# ATM90E3x-DB.net
KiCad netlist of a schematic drawn in Altium Designer
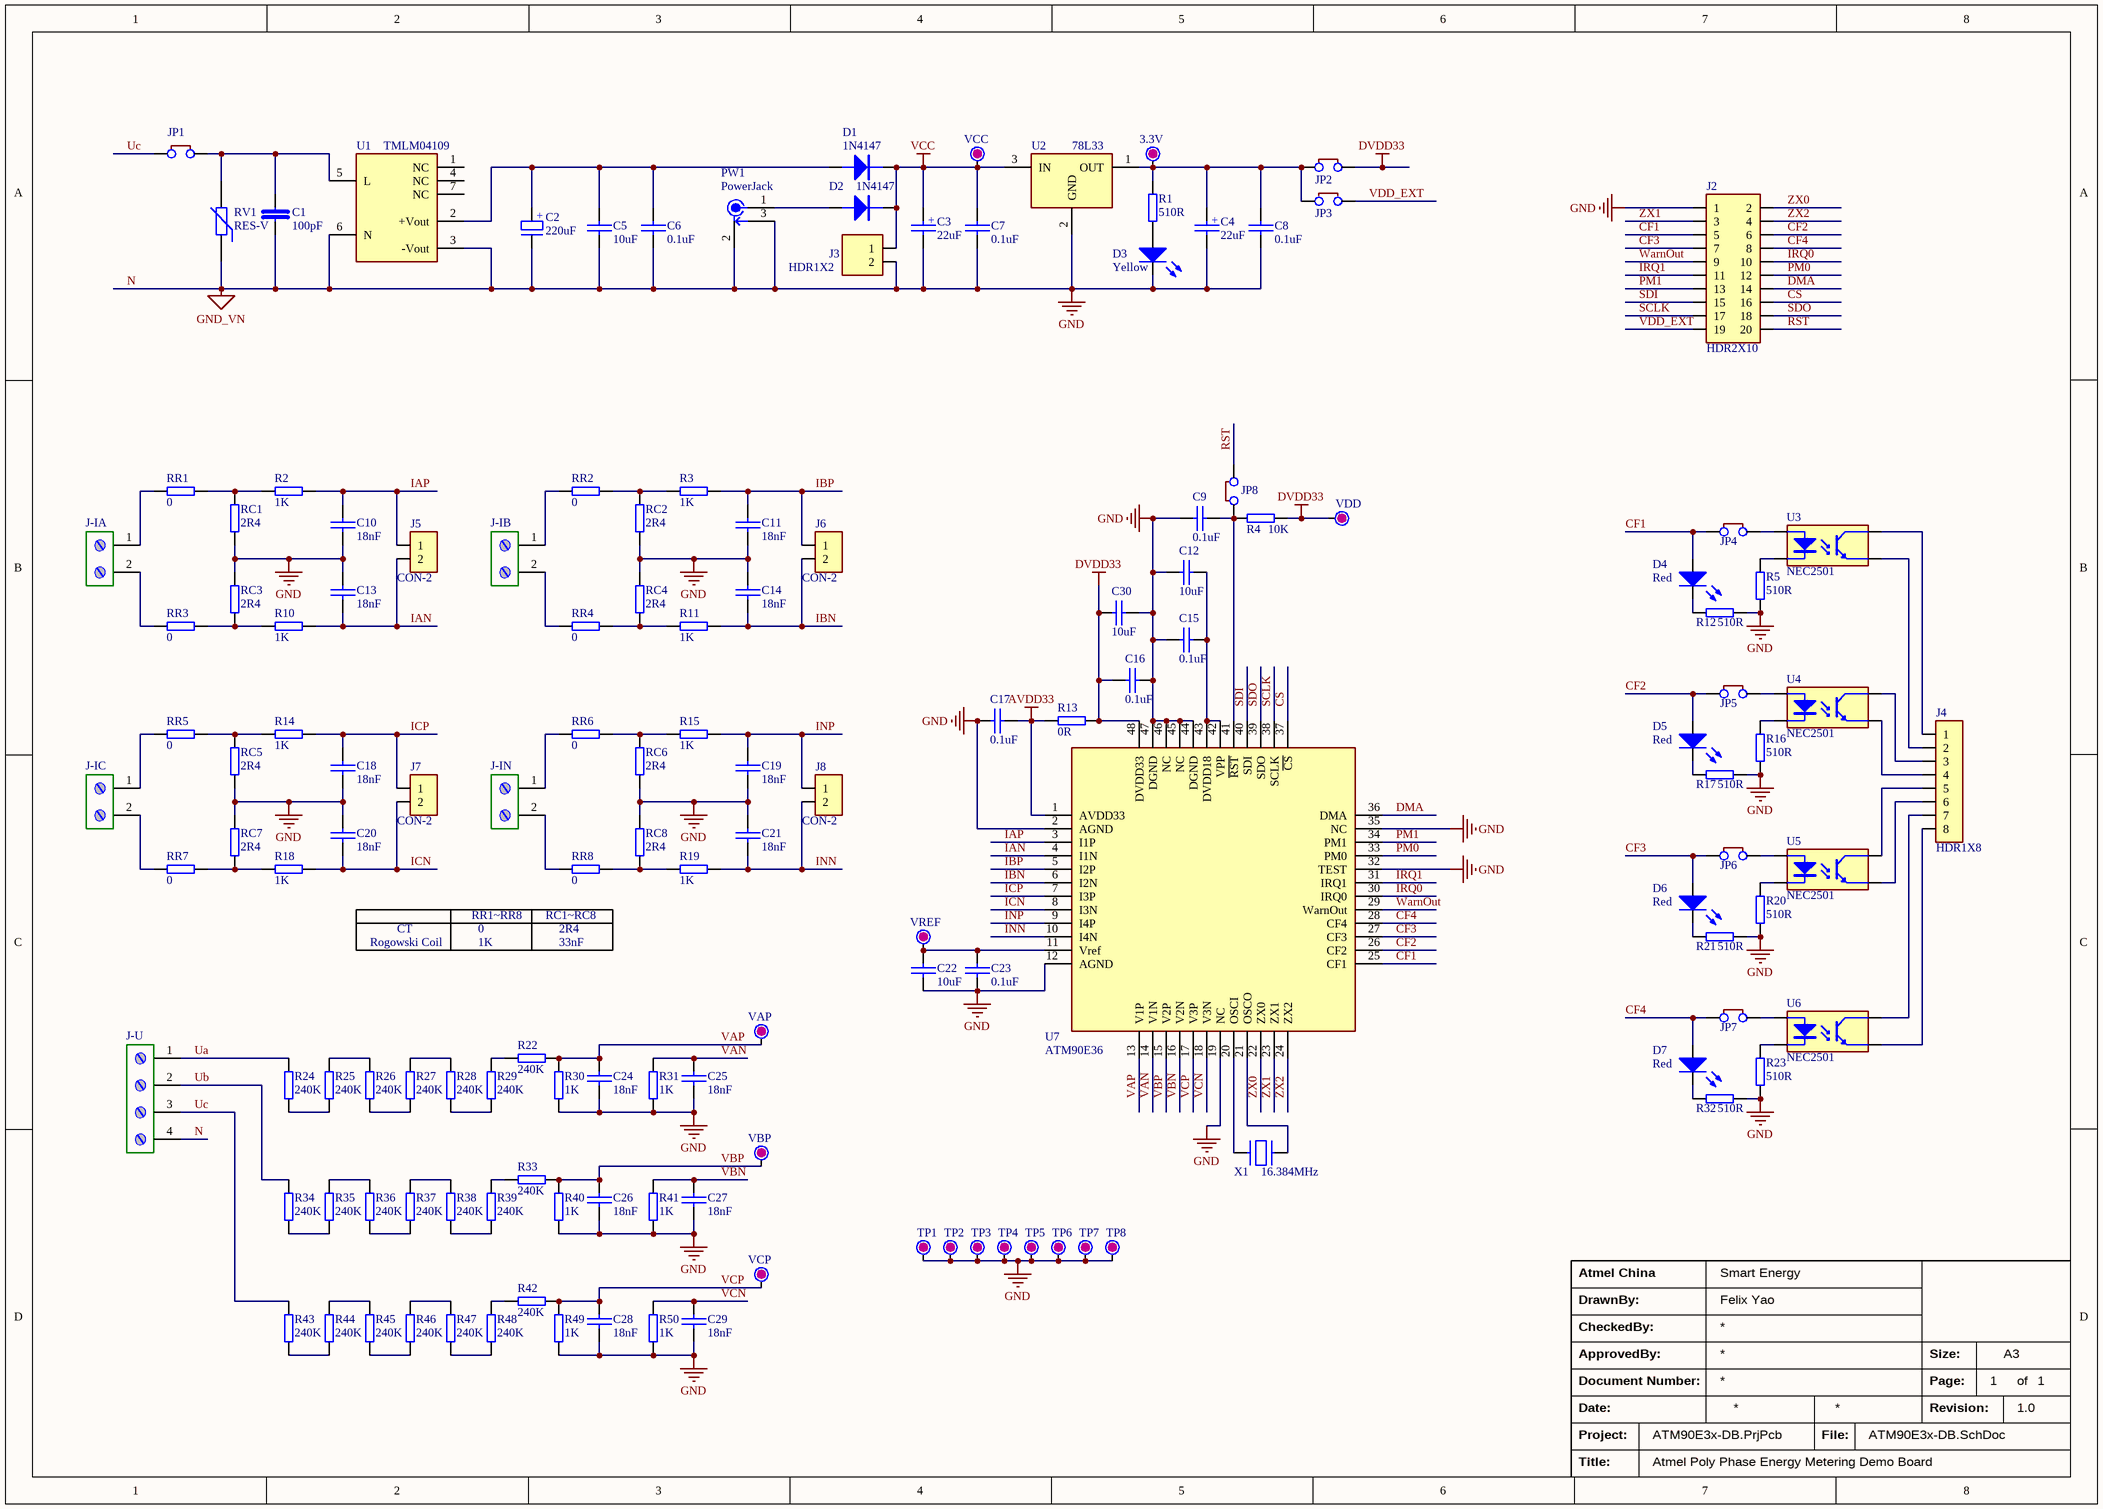
[diagram p0: ATM90E3x-DB.SchDoc]

(export (version "E")
  (design (tool "Eeschema 10.0.6"))
  (components
    (comp (ref "3.3V") (value "~") (footprint "TP") (libsource (lib "SchLib(AD10)") (part "TEST-POINT")))
    (comp (ref "C1")
      (value "100pF")
      (footprint "C_FILM_600")
      (libsource (lib "SchLib(AD10)") (part "CAP-FILM"))
    )
    (comp (ref "C2")
      (value "220uF")
      (footprint "C_ALUM_MIX_10x10")
      (libsource (lib "SchLib(AD10)") (part "CAP-ALUM"))
    )
    (comp (ref "C3")
      (value "22uF")
      (footprint "C_TANT_B3528")
      (libsource (lib "SchLib(AD10)") (part "CAP-TANT"))
    )
    (comp (ref "C4")
      (value "22uF")
      (footprint "C_TANT_B3528")
      (libsource (lib "SchLib(AD10)") (part "CAP-TANT"))
    )
    (comp (ref "C5") (value "10uF") (footprint "C0805") (libsource (lib "SchLib(AD10)") (part "CAP")))
    (comp (ref "C6") (value "0.1uF") (footprint "C0805") (libsource (lib "SchLib(AD10)") (part "CAP")))
    (comp (ref "C7") (value "0.1uF") (footprint "C0805") (libsource (lib "SchLib(AD10)") (part "CAP")))
    (comp (ref "C8") (value "0.1uF") (footprint "C0805") (libsource (lib "SchLib(AD10)") (part "CAP")))
    (comp (ref "C9") (value "0.1uF") (footprint "C0603") (libsource (lib "SchLib(AD10)") (part "CAP")))
    (comp (ref "C10") (value "18nF") (footprint "C0805") (libsource (lib "SchLib(AD10)") (part "CAP")))
    (comp (ref "C11") (value "18nF") (footprint "C0805") (libsource (lib "SchLib(AD10)") (part "CAP")))
    (comp (ref "C12") (value "10uF") (footprint "C0805") (libsource (lib "SchLib(AD10)") (part "CAP")))
    (comp (ref "C13") (value "18nF") (footprint "C0805") (libsource (lib "SchLib(AD10)") (part "CAP")))
    (comp (ref "C14") (value "18nF") (footprint "C0805") (libsource (lib "SchLib(AD10)") (part "CAP")))
    (comp (ref "C15") (value "0.1uF") (footprint "C0603") (libsource (lib "SchLib(AD10)") (part "CAP")))
    (comp (ref "C16") (value "0.1uF") (footprint "C0603") (libsource (lib "SchLib(AD10)") (part "CAP")))
    (comp (ref "C17") (value "0.1uF") (footprint "C0603") (libsource (lib "SchLib(AD10)") (part "CAP")))
    (comp (ref "C18") (value "18nF") (footprint "C0805") (libsource (lib "SchLib(AD10)") (part "CAP")))
    (comp (ref "C19") (value "18nF") (footprint "C0805") (libsource (lib "SchLib(AD10)") (part "CAP")))
    (comp (ref "C20") (value "18nF") (footprint "C0805") (libsource (lib "SchLib(AD10)") (part "CAP")))
    (comp (ref "C21") (value "18nF") (footprint "C0805") (libsource (lib "SchLib(AD10)") (part "CAP")))
    (comp (ref "C22") (value "10uF") (footprint "C0805") (libsource (lib "SchLib(AD10)") (part "CAP")))
    (comp (ref "C23") (value "0.1uF") (footprint "C0603") (libsource (lib "SchLib(AD10)") (part "CAP")))
    (comp (ref "C24") (value "18nF") (footprint "C0805") (libsource (lib "SchLib(AD10)") (part "CAP")))
    (comp (ref "C25") (value "18nF") (footprint "C0805") (libsource (lib "SchLib(AD10)") (part "CAP")))
    (comp (ref "C26") (value "18nF") (footprint "C0805") (libsource (lib "SchLib(AD10)") (part "CAP")))
    (comp (ref "C27") (value "18nF") (footprint "C0805") (libsource (lib "SchLib(AD10)") (part "CAP")))
    (comp (ref "C28") (value "18nF") (footprint "C0805") (libsource (lib "SchLib(AD10)") (part "CAP")))
    (comp (ref "C29") (value "18nF") (footprint "C0805") (libsource (lib "SchLib(AD10)") (part "CAP")))
    (comp (ref "C30") (value "10uF") (footprint "C0805") (libsource (lib "SchLib(AD10)") (part "CAP")))
    (comp (ref "D1")
      (value "1N4147")
      (footprint "SMA DO-214AC")
      (libsource (lib "SchLib(AD10)") (part "DIODE"))
    )
    (comp (ref "D2")
      (value "1N4147")
      (footprint "SMA DO-214AC")
      (libsource (lib "SchLib(AD10)") (part "DIODE"))
    )
    (comp (ref "D3") (value "Yellow") (footprint "LED-0805Y") (libsource (lib "SchLib(AD10)") (part "LED")))
    (comp (ref "D4") (value "Red") (footprint "LED-0805R") (libsource (lib "SchLib(AD10)") (part "LED")))
    (comp (ref "D5") (value "Red") (footprint "LED-0805R") (libsource (lib "SchLib(AD10)") (part "LED")))
    (comp (ref "D6") (value "Red") (footprint "LED-0805R") (libsource (lib "SchLib(AD10)") (part "LED")))
    (comp (ref "D7") (value "Red") (footprint "LED-0805R") (libsource (lib "SchLib(AD10)") (part "LED")))
    (comp (ref "J-IA")
      (value "~")
      (footprint "TE-1776119-2")
      (libsource (lib "SchLib(AD10)") (part "Terminal-Screw-2"))
    )
    (comp (ref "J-IB")
      (value "~")
      (footprint "TE-1776119-2")
      (libsource (lib "SchLib(AD10)") (part "Terminal-Screw-2"))
    )
    (comp (ref "J-IC")
      (value "~")
      (footprint "TE-1776119-2")
      (libsource (lib "SchLib(AD10)") (part "Terminal-Screw-2"))
    )
    (comp (ref "J-IN")
      (value "~")
      (footprint "TE-1776119-2")
      (libsource (lib "SchLib(AD10)") (part "Terminal-Screw-2"))
    )
    (comp (ref "J-U")
      (value "~")
      (footprint "TE-282843-4")
      (libsource (lib "SchLib(AD10)") (part "Terminal-Screw-4"))
    )
    (comp (ref "J2")
      (value "HDR2X10")
      (footprint "HDR2X10")
      (libsource (lib "SchLib(AD10)") (part "HDR2X10"))
    )
    (comp (ref "J3") (value "HDR1X2") (footprint "HDR1X2") (libsource (lib "SchLib(AD10)") (part "HDR1X2")))
    (comp (ref "J4") (value "HDR1X8") (footprint "HDR1X8") (libsource (lib "SchLib(AD10)") (part "HDR1X8")))
    (comp (ref "J5")
      (value "CON-2")
      (footprint "HDR1X2(uper)")
      (libsource (lib "SchLib(AD10)") (part "CON-2"))
    )
    (comp (ref "J6")
      (value "CON-2")
      (footprint "HDR1X2(uper)")
      (libsource (lib "SchLib(AD10)") (part "CON-2"))
    )
    (comp (ref "J7")
      (value "CON-2")
      (footprint "HDR1X2(uper)")
      (libsource (lib "SchLib(AD10)") (part "CON-2"))
    )
    (comp (ref "J8")
      (value "CON-2")
      (footprint "HDR1X2(uper)")
      (libsource (lib "SchLib(AD10)") (part "CON-2"))
    )
    (comp (ref "JP1") (value "JMP") (footprint "JMP-SMD") (libsource (lib "SchLib(AD10)") (part "JMP")))
    (comp (ref "JP2") (value "JMP") (footprint "JMP") (libsource (lib "SchLib(AD10)") (part "JMP")))
    (comp (ref "JP3") (value "JMP") (footprint "JMP") (libsource (lib "SchLib(AD10)") (part "JMP")))
    (comp (ref "JP4") (value "JMP") (footprint "JMP") (libsource (lib "SchLib(AD10)") (part "JMP")))
    (comp (ref "JP5") (value "JMP") (footprint "JMP") (libsource (lib "SchLib(AD10)") (part "JMP")))
    (comp (ref "JP6") (value "JMP") (footprint "JMP") (libsource (lib "SchLib(AD10)") (part "JMP")))
    (comp (ref "JP7") (value "JMP") (footprint "JMP") (libsource (lib "SchLib(AD10)") (part "JMP")))
    (comp (ref "JP8") (value "JMP") (footprint "JMP") (libsource (lib "SchLib(AD10)") (part "JMP")))
    (comp (ref "PW1")
      (value "PowerJack")
      (footprint "PowerJacket2.5")
      (libsource (lib "SchLib(AD10)") (part "PowerJack"))
    )
    (comp (ref "R1") (value "510R") (footprint "R0805") (libsource (lib "SchLib(AD10)") (part "RES")))
    (comp (ref "R2") (value "1K") (footprint "R0805") (libsource (lib "SchLib(AD10)") (part "RES")))
    (comp (ref "R3") (value "1K") (footprint "R0805") (libsource (lib "SchLib(AD10)") (part "RES")))
    (comp (ref "R4") (value "10K") (footprint "R0603") (libsource (lib "SchLib(AD10)") (part "RES")))
    (comp (ref "R5") (value "510R") (footprint "R0805") (libsource (lib "SchLib(AD10)") (part "RES")))
    (comp (ref "R10") (value "1K") (footprint "R0805") (libsource (lib "SchLib(AD10)") (part "RES")))
    (comp (ref "R11") (value "1K") (footprint "R0805") (libsource (lib "SchLib(AD10)") (part "RES")))
    (comp (ref "R12") (value "510R") (footprint "R0805") (libsource (lib "SchLib(AD10)") (part "RES")))
    (comp (ref "R13") (value "0R") (footprint "R0603") (libsource (lib "SchLib(AD10)") (part "RES")))
    (comp (ref "R14") (value "1K") (footprint "R0805") (libsource (lib "SchLib(AD10)") (part "RES")))
    (comp (ref "R15") (value "1K") (footprint "R0805") (libsource (lib "SchLib(AD10)") (part "RES")))
    (comp (ref "R16") (value "510R") (footprint "R0805") (libsource (lib "SchLib(AD10)") (part "RES")))
    (comp (ref "R17") (value "510R") (footprint "R0805") (libsource (lib "SchLib(AD10)") (part "RES")))
    (comp (ref "R18") (value "1K") (footprint "R0805") (libsource (lib "SchLib(AD10)") (part "RES")))
    (comp (ref "R19") (value "1K") (footprint "R0805") (libsource (lib "SchLib(AD10)") (part "RES")))
    (comp (ref "R20") (value "510R") (footprint "R0805") (libsource (lib "SchLib(AD10)") (part "RES")))
    (comp (ref "R21") (value "510R") (footprint "R0805") (libsource (lib "SchLib(AD10)") (part "RES")))
    (comp (ref "R22") (value "240K") (footprint "R1206") (libsource (lib "SchLib(AD10)") (part "RES")))
    (comp (ref "R23") (value "510R") (footprint "R0805") (libsource (lib "SchLib(AD10)") (part "RES")))
    (comp (ref "R24") (value "240K") (footprint "R1206") (libsource (lib "SchLib(AD10)") (part "RES")))
    (comp (ref "R25") (value "240K") (footprint "R1206") (libsource (lib "SchLib(AD10)") (part "RES")))
    (comp (ref "R26") (value "240K") (footprint "R1206") (libsource (lib "SchLib(AD10)") (part "RES")))
    (comp (ref "R27") (value "240K") (footprint "R1206") (libsource (lib "SchLib(AD10)") (part "RES")))
    (comp (ref "R28") (value "240K") (footprint "R1206") (libsource (lib "SchLib(AD10)") (part "RES")))
    (comp (ref "R29") (value "240K") (footprint "R1206") (libsource (lib "SchLib(AD10)") (part "RES")))
    (comp (ref "R30") (value "1K") (footprint "R0805") (libsource (lib "SchLib(AD10)") (part "RES")))
    (comp (ref "R31") (value "1K") (footprint "R0805") (libsource (lib "SchLib(AD10)") (part "RES")))
    (comp (ref "R32") (value "510R") (footprint "R0805") (libsource (lib "SchLib(AD10)") (part "RES")))
    (comp (ref "R33") (value "240K") (footprint "R1206") (libsource (lib "SchLib(AD10)") (part "RES")))
    (comp (ref "R34") (value "240K") (footprint "R1206") (libsource (lib "SchLib(AD10)") (part "RES")))
    (comp (ref "R35") (value "240K") (footprint "R1206") (libsource (lib "SchLib(AD10)") (part "RES")))
    (comp (ref "R36") (value "240K") (footprint "R1206") (libsource (lib "SchLib(AD10)") (part "RES")))
    (comp (ref "R37") (value "240K") (footprint "R1206") (libsource (lib "SchLib(AD10)") (part "RES")))
    (comp (ref "R38") (value "240K") (footprint "R1206") (libsource (lib "SchLib(AD10)") (part "RES")))
    (comp (ref "R39") (value "240K") (footprint "R1206") (libsource (lib "SchLib(AD10)") (part "RES")))
    (comp (ref "R40") (value "1K") (footprint "R0805") (libsource (lib "SchLib(AD10)") (part "RES")))
    (comp (ref "R41") (value "1K") (footprint "R0805") (libsource (lib "SchLib(AD10)") (part "RES")))
    (comp (ref "R42") (value "240K") (footprint "R1206") (libsource (lib "SchLib(AD10)") (part "RES")))
    (comp (ref "R43") (value "240K") (footprint "R1206") (libsource (lib "SchLib(AD10)") (part "RES")))
    (comp (ref "R44") (value "240K") (footprint "R1206") (libsource (lib "SchLib(AD10)") (part "RES")))
    (comp (ref "R45") (value "240K") (footprint "R1206") (libsource (lib "SchLib(AD10)") (part "RES")))
    (comp (ref "R46") (value "240K") (footprint "R1206") (libsource (lib "SchLib(AD10)") (part "RES")))
    (comp (ref "R47") (value "240K") (footprint "R1206") (libsource (lib "SchLib(AD10)") (part "RES")))
    (comp (ref "R48") (value "240K") (footprint "R1206") (libsource (lib "SchLib(AD10)") (part "RES")))
    (comp (ref "R49") (value "1K") (footprint "R0805") (libsource (lib "SchLib(AD10)") (part "RES")))
    (comp (ref "R50") (value "1K") (footprint "R0805") (libsource (lib "SchLib(AD10)") (part "RES")))
    (comp (ref "RC1") (value "2R4") (footprint "R0805") (libsource (lib "SchLib(AD10)") (part "RES")))
    (comp (ref "RC2") (value "2R4") (footprint "R0805") (libsource (lib "SchLib(AD10)") (part "RES")))
    (comp (ref "RC3") (value "2R4") (footprint "R0805") (libsource (lib "SchLib(AD10)") (part "RES")))
    (comp (ref "RC4") (value "2R4") (footprint "R0805") (libsource (lib "SchLib(AD10)") (part "RES")))
    (comp (ref "RC5") (value "2R4") (footprint "R0805") (libsource (lib "SchLib(AD10)") (part "RES")))
    (comp (ref "RC6") (value "2R4") (footprint "R0805") (libsource (lib "SchLib(AD10)") (part "RES")))
    (comp (ref "RC7") (value "2R4") (footprint "R0805") (libsource (lib "SchLib(AD10)") (part "RES")))
    (comp (ref "RC8") (value "2R4") (footprint "R0805") (libsource (lib "SchLib(AD10)") (part "RES")))
    (comp (ref "RR1") (value "0") (footprint "R0805") (libsource (lib "SchLib(AD10)") (part "RES")))
    (comp (ref "RR2") (value "0") (footprint "R0805") (libsource (lib "SchLib(AD10)") (part "RES")))
    (comp (ref "RR3") (value "0") (footprint "R0805") (libsource (lib "SchLib(AD10)") (part "RES")))
    (comp (ref "RR4") (value "0") (footprint "R0805") (libsource (lib "SchLib(AD10)") (part "RES")))
    (comp (ref "RR5") (value "0") (footprint "R0805") (libsource (lib "SchLib(AD10)") (part "RES")))
    (comp (ref "RR6") (value "0") (footprint "R0805") (libsource (lib "SchLib(AD10)") (part "RES")))
    (comp (ref "RR7") (value "0") (footprint "R0805") (libsource (lib "SchLib(AD10)") (part "RES")))
    (comp (ref "RR8") (value "0") (footprint "R0805") (libsource (lib "SchLib(AD10)") (part "RES")))
    (comp (ref "RV1")
      (value "RES-V")
      (footprint "VDRS10P510BSE")
      (libsource (lib "SchLib(AD10)") (part "RES-V"))
    )
    (comp (ref "TP1") (value "GND") (footprint "TP") (libsource (lib "SchLib(AD10)") (part "TEST-POINT")))
    (comp (ref "TP2") (value "GND") (footprint "TP") (libsource (lib "SchLib(AD10)") (part "TEST-POINT")))
    (comp (ref "TP3") (value "GND") (footprint "TP") (libsource (lib "SchLib(AD10)") (part "TEST-POINT")))
    (comp (ref "TP4") (value "GND") (footprint "TP") (libsource (lib "SchLib(AD10)") (part "TEST-POINT")))
    (comp (ref "TP5") (value "GND") (footprint "TP-SMD") (libsource (lib "SchLib(AD10)") (part "TEST-POINT")))
    (comp (ref "TP6") (value "GND") (footprint "TP-SMD") (libsource (lib "SchLib(AD10)") (part "TEST-POINT")))
    (comp (ref "TP7") (value "GND") (footprint "TP-SMD") (libsource (lib "SchLib(AD10)") (part "TEST-POINT")))
    (comp (ref "TP8") (value "GND") (footprint "TP-SMD") (libsource (lib "SchLib(AD10)") (part "TEST-POINT")))
    (comp (ref "U1")
      (value "TMLM04109")
      (footprint "TMLM04112")
      (libsource (lib "SchLib(AD10)") (part "TMLM04112"))
    )
    (comp (ref "U2") (value "78L33") (footprint "SOT-89") (libsource (lib "SchLib(AD10)") (part "78LXX")))
    (comp (ref "U3")
      (value "NEC2501")
      (footprint "PS2501L-1")
      (libsource (lib "SchLib(AD10)") (part "NEC2501"))
    )
    (comp (ref "U4")
      (value "NEC2501")
      (footprint "PS2501L-1")
      (libsource (lib "SchLib(AD10)") (part "NEC2501"))
    )
    (comp (ref "U5")
      (value "NEC2501")
      (footprint "PS2501L-1")
      (libsource (lib "SchLib(AD10)") (part "NEC2501"))
    )
    (comp (ref "U6")
      (value "NEC2501")
      (footprint "PS2501L-1")
      (libsource (lib "SchLib(AD10)") (part "NEC2501"))
    )
    (comp (ref "U7")
      (value "ATM90E36")
      (footprint "TQFP-48(7x7)")
      (description "ATM90E3X")
      (libsource (lib "SchLib(AD10)") (part "ATM90E3X"))
    )
    (comp (ref "VAP") (value "~") (footprint "TP") (libsource (lib "SchLib(AD10)") (part "TEST-POINT")))
    (comp (ref "VBP") (value "~") (footprint "TP") (libsource (lib "SchLib(AD10)") (part "TEST-POINT")))
    (comp (ref "VCC") (value "~") (footprint "TP") (libsource (lib "SchLib(AD10)") (part "TEST-POINT")))
    (comp (ref "VCP") (value "~") (footprint "TP") (libsource (lib "SchLib(AD10)") (part "TEST-POINT")))
    (comp (ref "VDD") (value "~") (footprint "TP") (libsource (lib "SchLib(AD10)") (part "TEST-POINT")))
    (comp (ref "VREF") (value "~") (footprint "TP") (libsource (lib "SchLib(AD10)") (part "TEST-POINT")))
    (comp (ref "X1")
      (value "16.384MHz")
      (footprint "XTAL-MIX-49")
      (libsource (lib "SchLib(AD10)") (part "XTAL-T"))
    )
  )
  (nets
    (net (code "1") (name "/CF1") (class "Default")
      (node (ref "D4") (pin "A") (pinfunction "A_A") (pintype "passive"))
      (node (ref "J2") (pin "5") (pinfunction "5_5") (pintype "passive"))
      (node (ref "JP4") (pin "1") (pinfunction "1_1") (pintype "passive"))
      (node (ref "U7") (pin "25") (pinfunction "CF1_25") (pintype "passive"))
    )
    (net (code "2") (name "/CF2") (class "Default")
      (node (ref "D5") (pin "A") (pinfunction "A_A") (pintype "passive"))
      (node (ref "J2") (pin "6") (pinfunction "6_6") (pintype "passive"))
      (node (ref "JP5") (pin "1") (pinfunction "1_1") (pintype "passive"))
      (node (ref "U7") (pin "26") (pinfunction "CF2_26") (pintype "passive"))
    )
    (net (code "3") (name "/CF3") (class "Default")
      (node (ref "D6") (pin "A") (pinfunction "A_A") (pintype "passive"))
      (node (ref "J2") (pin "7") (pinfunction "7_7") (pintype "passive"))
      (node (ref "JP6") (pin "1") (pinfunction "1_1") (pintype "passive"))
      (node (ref "U7") (pin "27") (pinfunction "CF3_27") (pintype "passive"))
    )
    (net (code "4") (name "/CF4") (class "Default")
      (node (ref "D7") (pin "A") (pinfunction "A_A") (pintype "passive"))
      (node (ref "J2") (pin "8") (pinfunction "8_8") (pintype "passive"))
      (node (ref "JP7") (pin "1") (pinfunction "1_1") (pintype "passive"))
      (node (ref "U7") (pin "28") (pinfunction "CF4_28") (pintype "passive"))
    )
    (net (code "5") (name "/CS") (class "Default")
      (node (ref "J2") (pin "16") (pinfunction "16_16") (pintype "passive"))
      (node (ref "U7") (pin "37") (pinfunction "~{CS}_37") (pintype "passive"))
    )
    (net (code "6") (name "/DMA") (class "Default")
      (node (ref "J2") (pin "14") (pinfunction "14_14") (pintype "passive"))
      (node (ref "U7") (pin "36") (pinfunction "DMA_36") (pintype "passive"))
    )
    (net (code "7") (name "/IAN") (class "Default")
      (node (ref "C13") (pin "1") (pintype "passive"))
      (node (ref "J5") (pin "2") (pinfunction "2_2") (pintype "passive"))
      (node (ref "R10") (pin "1") (pinfunction "1_1") (pintype "passive"))
      (node (ref "U7") (pin "4") (pinfunction "I1N_4") (pintype "passive"))
    )
    (net (code "8") (name "/IAP") (class "Default")
      (node (ref "C10") (pin "2") (pintype "passive"))
      (node (ref "J5") (pin "1") (pinfunction "1_1") (pintype "passive"))
      (node (ref "R2") (pin "1") (pinfunction "1_1") (pintype "passive"))
      (node (ref "U7") (pin "3") (pinfunction "I1P_3") (pintype "passive"))
    )
    (net (code "9") (name "/IBN") (class "Default")
      (node (ref "C14") (pin "2") (pintype "passive"))
      (node (ref "J6") (pin "2") (pinfunction "2_2") (pintype "passive"))
      (node (ref "R11") (pin "2") (pinfunction "2_2") (pintype "passive"))
      (node (ref "U7") (pin "6") (pinfunction "I2N_6") (pintype "passive"))
    )
    (net (code "10") (name "/IBP") (class "Default")
      (node (ref "C11") (pin "1") (pintype "passive"))
      (node (ref "J6") (pin "1") (pinfunction "1_1") (pintype "passive"))
      (node (ref "R3") (pin "2") (pinfunction "2_2") (pintype "passive"))
      (node (ref "U7") (pin "5") (pinfunction "I2P_5") (pintype "passive"))
    )
    (net (code "11") (name "/ICN") (class "Default")
      (node (ref "C20") (pin "2") (pintype "passive"))
      (node (ref "J7") (pin "2") (pinfunction "2_2") (pintype "passive"))
      (node (ref "R18") (pin "2") (pinfunction "2_2") (pintype "passive"))
      (node (ref "U7") (pin "8") (pinfunction "I3N_8") (pintype "passive"))
    )
    (net (code "12") (name "/ICP") (class "Default")
      (node (ref "C18") (pin "1") (pintype "passive"))
      (node (ref "J7") (pin "1") (pinfunction "1_1") (pintype "passive"))
      (node (ref "R14") (pin "2") (pinfunction "2_2") (pintype "passive"))
      (node (ref "U7") (pin "7") (pinfunction "I3P_7") (pintype "passive"))
    )
    (net (code "13") (name "/INN") (class "Default")
      (node (ref "C21") (pin "2") (pintype "passive"))
      (node (ref "J8") (pin "2") (pinfunction "2_2") (pintype "passive"))
      (node (ref "R19") (pin "2") (pinfunction "2_2") (pintype "passive"))
      (node (ref "U7") (pin "10") (pinfunction "I4N_10") (pintype "passive"))
    )
    (net (code "14") (name "/INP") (class "Default")
      (node (ref "C19") (pin "1") (pintype "passive"))
      (node (ref "J8") (pin "1") (pinfunction "1_1") (pintype "passive"))
      (node (ref "R15") (pin "2") (pinfunction "2_2") (pintype "passive"))
      (node (ref "U7") (pin "9") (pinfunction "I4P_9") (pintype "passive"))
    )
    (net (code "15") (name "/IRQ0") (class "Default")
      (node (ref "J2") (pin "10") (pinfunction "10_10") (pintype "passive"))
      (node (ref "U7") (pin "30") (pinfunction "IRQ0_30") (pintype "passive"))
    )
    (net (code "16") (name "/IRQ1") (class "Default")
      (node (ref "J2") (pin "11") (pinfunction "11_11") (pintype "passive"))
      (node (ref "U7") (pin "31") (pinfunction "IRQ1_31") (pintype "passive"))
    )
    (net (code "17") (name "/PM0") (class "Default")
      (node (ref "J2") (pin "12") (pinfunction "12_12") (pintype "passive"))
      (node (ref "U7") (pin "33") (pinfunction "PM0_33") (pintype "passive"))
    )
    (net (code "18") (name "/PM1") (class "Default")
      (node (ref "J2") (pin "13") (pinfunction "13_13") (pintype "passive"))
      (node (ref "U7") (pin "34") (pinfunction "PM1_34") (pintype "passive"))
    )
    (net (code "19") (name "/RST") (class "Default")
      (node (ref "J2") (pin "20") (pinfunction "20_20") (pintype "passive"))
      (node (ref "JP8") (pin "2") (pinfunction "2_2") (pintype "passive"))
    )
    (net (code "20") (name "/SCLK") (class "Default")
      (node (ref "J2") (pin "17") (pinfunction "17_17") (pintype "passive"))
      (node (ref "U7") (pin "38") (pinfunction "SCLK_38") (pintype "passive"))
    )
    (net (code "21") (name "/SDI") (class "Default")
      (node (ref "J2") (pin "15") (pinfunction "15_15") (pintype "passive"))
      (node (ref "U7") (pin "40") (pinfunction "SDI_40") (pintype "passive"))
    )
    (net (code "22") (name "/SDO") (class "Default")
      (node (ref "J2") (pin "18") (pinfunction "18_18") (pintype "passive"))
      (node (ref "U7") (pin "39") (pinfunction "SDO_39") (pintype "passive"))
    )
    (net (code "23") (name "/Ua") (class "Default")
      (node (ref "J-U") (pin "1") (pinfunction "1_1") (pintype "passive"))
      (node (ref "R24") (pin "1") (pinfunction "1_1") (pintype "passive"))
    )
    (net (code "24") (name "/Ub") (class "Default")
      (node (ref "J-U") (pin "2") (pinfunction "2_2") (pintype "passive"))
      (node (ref "R34") (pin "2") (pinfunction "2_2") (pintype "passive"))
    )
    (net (code "25") (name "/Uc") (class "Default")
      (node (ref "J-U") (pin "3") (pinfunction "3_3") (pintype "passive"))
      (node (ref "JP1") (pin "1") (pinfunction "1_1") (pintype "passive"))
      (node (ref "R43") (pin "2") (pinfunction "2_2") (pintype "passive"))
    )
    (net (code "26") (name "/VAN") (class "Default")
      (node (ref "C25") (pin "2") (pintype "passive"))
      (node (ref "R31") (pin "2") (pinfunction "2_2") (pintype "passive"))
      (node (ref "U7") (pin "14") (pinfunction "V1N_14") (pintype "passive"))
    )
    (net (code "27") (name "/VAP") (class "Default")
      (node (ref "C24") (pin "2") (pintype "passive"))
      (node (ref "R22") (pin "2") (pinfunction "2_2") (pintype "passive"))
      (node (ref "R30") (pin "2") (pinfunction "2_2") (pintype "passive"))
      (node (ref "U7") (pin "13") (pinfunction "V1P_13") (pintype "passive"))
      (node (ref "VAP") (pin "1") (pinfunction "1_1") (pintype "passive"))
    )
    (net (code "28") (name "/VBN") (class "Default")
      (node (ref "C27") (pin "2") (pintype "passive"))
      (node (ref "R41") (pin "2") (pinfunction "2_2") (pintype "passive"))
      (node (ref "U7") (pin "16") (pinfunction "V2N_16") (pintype "passive"))
    )
    (net (code "29") (name "/VBP") (class "Default")
      (node (ref "C26") (pin "2") (pintype "passive"))
      (node (ref "R33") (pin "1") (pinfunction "1_1") (pintype "passive"))
      (node (ref "R40") (pin "2") (pinfunction "2_2") (pintype "passive"))
      (node (ref "U7") (pin "15") (pinfunction "V2P_15") (pintype "passive"))
      (node (ref "VBP") (pin "1") (pinfunction "1_1") (pintype "passive"))
    )
    (net (code "30") (name "/VCN") (class "Default")
      (node (ref "C29") (pin "2") (pintype "passive"))
      (node (ref "R50") (pin "2") (pinfunction "2_2") (pintype "passive"))
      (node (ref "U7") (pin "18") (pinfunction "V3N_18") (pintype "passive"))
    )
    (net (code "31") (name "/VCP") (class "Default")
      (node (ref "C28") (pin "2") (pintype "passive"))
      (node (ref "R42") (pin "1") (pinfunction "1_1") (pintype "passive"))
      (node (ref "R49") (pin "2") (pinfunction "2_2") (pintype "passive"))
      (node (ref "U7") (pin "17") (pinfunction "V3P_17") (pintype "passive"))
      (node (ref "VCP") (pin "1") (pinfunction "1_1") (pintype "passive"))
    )
    (net (code "32") (name "/VDD_EXT") (class "Default")
      (node (ref "J2") (pin "19") (pinfunction "19_19") (pintype "passive"))
      (node (ref "JP3") (pin "2") (pinfunction "2_2") (pintype "passive"))
    )
    (net (code "33") (name "/WarnOut") (class "Default")
      (node (ref "J2") (pin "9") (pinfunction "9_9") (pintype "passive"))
      (node (ref "U7") (pin "29") (pinfunction "WarnOut_29") (pintype "passive"))
    )
    (net (code "34") (name "/ZX0") (class "Default")
      (node (ref "J2") (pin "2") (pinfunction "2_2") (pintype "passive"))
      (node (ref "U7") (pin "22") (pinfunction "ZX0_22") (pintype "passive"))
    )
    (net (code "35") (name "/ZX1") (class "Default")
      (node (ref "J2") (pin "3") (pinfunction "3_3") (pintype "passive"))
      (node (ref "U7") (pin "23") (pinfunction "ZX1_23") (pintype "passive"))
    )
    (net (code "36") (name "/ZX2") (class "Default")
      (node (ref "J2") (pin "4") (pinfunction "4_4") (pintype "passive"))
      (node (ref "U7") (pin "24") (pinfunction "ZX2_24") (pintype "passive"))
    )
    (net (code "37") (name "AVDD33") (class "Default")
      (node (ref "C17") (pin "2") (pintype "passive"))
      (node (ref "R13") (pin "2") (pinfunction "2_2") (pintype "passive"))
      (node (ref "U7") (pin "1") (pinfunction "AVDD33_1") (pintype "passive"))
    )
    (net (code "38") (name "DVDD33") (class "Default")
      (node (ref "C16") (pin "1") (pintype "passive"))
      (node (ref "C30") (pin "2") (pintype "passive"))
      (node (ref "JP2") (pin "2") (pinfunction "2_2") (pintype "passive"))
      (node (ref "R13") (pin "1") (pinfunction "1_1") (pintype "passive"))
      (node (ref "R4") (pin "2") (pinfunction "2_2") (pintype "passive"))
      (node (ref "U7") (pin "48") (pinfunction "DVDD33_48") (pintype "passive"))
      (node (ref "VDD") (pin "1") (pinfunction "1_1") (pintype "passive"))
    )
    (net (code "39") (name "GND") (class "Default")
      (node (ref "C1") (pin "1") (pintype "passive"))
      (node (ref "C10") (pin "1") (pintype "passive"))
      (node (ref "C11") (pin "2") (pintype "passive"))
      (node (ref "C12") (pin "2") (pintype "passive"))
      (node (ref "C13") (pin "2") (pintype "passive"))
      (node (ref "C14") (pin "1") (pintype "passive"))
      (node (ref "C15") (pin "1") (pintype "passive"))
      (node (ref "C16") (pin "2") (pintype "passive"))
      (node (ref "C17") (pin "1") (pintype "passive"))
      (node (ref "C18") (pin "2") (pintype "passive"))
      (node (ref "C19") (pin "2") (pintype "passive"))
      (node (ref "C2") (pin "2") (pinfunction "2_2") (pintype "passive"))
      (node (ref "C20") (pin "1") (pintype "passive"))
      (node (ref "C21") (pin "1") (pintype "passive"))
      (node (ref "C22") (pin "1") (pintype "passive"))
      (node (ref "C23") (pin "1") (pintype "passive"))
      (node (ref "C24") (pin "1") (pintype "passive"))
      (node (ref "C25") (pin "1") (pintype "passive"))
      (node (ref "C26") (pin "1") (pintype "passive"))
      (node (ref "C27") (pin "1") (pintype "passive"))
      (node (ref "C28") (pin "1") (pintype "passive"))
      (node (ref "C29") (pin "1") (pintype "passive"))
      (node (ref "C3") (pin "2") (pintype "passive"))
      (node (ref "C30") (pin "1") (pintype "passive"))
      (node (ref "C4") (pin "2") (pintype "passive"))
      (node (ref "C5") (pin "1") (pintype "passive"))
      (node (ref "C6") (pin "1") (pintype "passive"))
      (node (ref "C7") (pin "1") (pintype "passive"))
      (node (ref "C8") (pin "1") (pintype "passive"))
      (node (ref "C9") (pin "1") (pintype "passive"))
      (node (ref "D3") (pin "K") (pinfunction "K_K") (pintype "passive"))
      (node (ref "J-U") (pin "4") (pinfunction "4_4") (pintype "passive"))
      (node (ref "J2") (pin "1") (pinfunction "1_1") (pintype "passive"))
      (node (ref "J3") (pin "2") (pinfunction "2_2") (pintype "passive"))
      (node (ref "PW1") (pin "2") (pinfunction "2_2") (pintype "passive"))
      (node (ref "PW1") (pin "3") (pinfunction "3_3") (pintype "passive"))
      (node (ref "R12") (pin "1") (pinfunction "1_1") (pintype "passive"))
      (node (ref "R16") (pin "1") (pinfunction "1_1") (pintype "passive"))
      (node (ref "R17") (pin "1") (pinfunction "1_1") (pintype "passive"))
      (node (ref "R20") (pin "1") (pinfunction "1_1") (pintype "passive"))
      (node (ref "R21") (pin "1") (pinfunction "1_1") (pintype "passive"))
      (node (ref "R23") (pin "1") (pinfunction "1_1") (pintype "passive"))
      (node (ref "R30") (pin "1") (pinfunction "1_1") (pintype "passive"))
      (node (ref "R31") (pin "1") (pinfunction "1_1") (pintype "passive"))
      (node (ref "R32") (pin "1") (pinfunction "1_1") (pintype "passive"))
      (node (ref "R40") (pin "1") (pinfunction "1_1") (pintype "passive"))
      (node (ref "R41") (pin "1") (pinfunction "1_1") (pintype "passive"))
      (node (ref "R49") (pin "1") (pinfunction "1_1") (pintype "passive"))
      (node (ref "R5") (pin "1") (pinfunction "1_1") (pintype "passive"))
      (node (ref "R50") (pin "1") (pinfunction "1_1") (pintype "passive"))
      (node (ref "RC1") (pin "1") (pinfunction "1_1") (pintype "passive"))
      (node (ref "RC2") (pin "1") (pinfunction "1_1") (pintype "passive"))
      (node (ref "RC3") (pin "2") (pinfunction "2_2") (pintype "passive"))
      (node (ref "RC4") (pin "2") (pinfunction "2_2") (pintype "passive"))
      (node (ref "RC5") (pin "1") (pinfunction "1_1") (pintype "passive"))
      (node (ref "RC6") (pin "1") (pinfunction "1_1") (pintype "passive"))
      (node (ref "RC7") (pin "2") (pinfunction "2_2") (pintype "passive"))
      (node (ref "RC8") (pin "2") (pinfunction "2_2") (pintype "passive"))
      (node (ref "RV1") (pin "1") (pinfunction "1_1") (pintype "passive"))
      (node (ref "TP1") (pin "1") (pinfunction "1_1") (pintype "passive"))
      (node (ref "TP2") (pin "1") (pinfunction "1_1") (pintype "passive"))
      (node (ref "TP3") (pin "1") (pinfunction "1_1") (pintype "passive"))
      (node (ref "TP4") (pin "1") (pinfunction "1_1") (pintype "passive"))
      (node (ref "TP5") (pin "1") (pinfunction "1_1") (pintype "passive"))
      (node (ref "TP6") (pin "1") (pinfunction "1_1") (pintype "passive"))
      (node (ref "TP7") (pin "1") (pinfunction "1_1") (pintype "passive"))
      (node (ref "TP8") (pin "1") (pinfunction "1_1") (pintype "passive"))
      (node (ref "U1") (pin "3") (pinfunction "-Vout_3") (pintype "passive"))
      (node (ref "U1") (pin "6") (pinfunction "N_6") (pintype "passive"))
      (node (ref "U2") (pin "2") (pinfunction "GND_2") (pintype "passive"))
      (node (ref "U7") (pin "12") (pinfunction "AGND_12") (pintype "passive"))
      (node (ref "U7") (pin "19") (pinfunction "NC_19") (pintype "passive"))
      (node (ref "U7") (pin "2") (pinfunction "AGND_2") (pintype "passive"))
      (node (ref "U7") (pin "32") (pinfunction "TEST_32") (pintype "passive"))
      (node (ref "U7") (pin "35") (pinfunction "NC_35") (pintype "passive"))
      (node (ref "U7") (pin "44") (pinfunction "DGND_44") (pintype "passive"))
      (node (ref "U7") (pin "45") (pinfunction "NC_45") (pintype "passive"))
      (node (ref "U7") (pin "46") (pinfunction "NC_46") (pintype "passive"))
      (node (ref "U7") (pin "47") (pinfunction "DGND_47") (pintype "passive"))
    )
    (net (code "40") (name "Net-(D2-PadA)") (class "Default")
      (node (ref "D2") (pin "A") (pintype "passive"))
      (node (ref "PW1") (pin "1") (pinfunction "1_1") (pintype "passive"))
    )
    (net (code "41") (name "Net-(D3-PadA)") (class "Default")
      (node (ref "D3") (pin "A") (pinfunction "A_A") (pintype "passive"))
      (node (ref "R1") (pin "1") (pinfunction "1_1") (pintype "passive"))
    )
    (net (code "42") (name "Net-(D4-PadK)") (class "Default")
      (node (ref "D4") (pin "K") (pinfunction "K_K") (pintype "passive"))
      (node (ref "R12") (pin "2") (pinfunction "2_2") (pintype "passive"))
    )
    (net (code "43") (name "Net-(D5-PadK)") (class "Default")
      (node (ref "D5") (pin "K") (pinfunction "K_K") (pintype "passive"))
      (node (ref "R17") (pin "2") (pinfunction "2_2") (pintype "passive"))
    )
    (net (code "44") (name "Net-(D6-PadK)") (class "Default")
      (node (ref "D6") (pin "K") (pinfunction "K_K") (pintype "passive"))
      (node (ref "R21") (pin "2") (pinfunction "2_2") (pintype "passive"))
    )
    (net (code "45") (name "Net-(D7-PadK)") (class "Default")
      (node (ref "D7") (pin "K") (pinfunction "K_K") (pintype "passive"))
      (node (ref "R32") (pin "2") (pinfunction "2_2") (pintype "passive"))
    )
    (net (code "46") (name "Net-(J-IA-Pad1)") (class "Default")
      (node (ref "J-IA") (pin "1") (pinfunction "1_1") (pintype "passive"))
      (node (ref "RR1") (pin "2") (pinfunction "2_2") (pintype "passive"))
    )
    (net (code "47") (name "Net-(J-IA-Pad2)") (class "Default")
      (node (ref "J-IA") (pin "2") (pinfunction "2_2") (pintype "passive"))
      (node (ref "RR3") (pin "2") (pinfunction "2_2") (pintype "passive"))
    )
    (net (code "48") (name "Net-(J-IB-Pad1)") (class "Default")
      (node (ref "J-IB") (pin "1") (pinfunction "1_1") (pintype "passive"))
      (node (ref "RR2") (pin "2") (pinfunction "2_2") (pintype "passive"))
    )
    (net (code "49") (name "Net-(J-IB-Pad2)") (class "Default")
      (node (ref "J-IB") (pin "2") (pinfunction "2_2") (pintype "passive"))
      (node (ref "RR4") (pin "2") (pinfunction "2_2") (pintype "passive"))
    )
    (net (code "50") (name "Net-(J-IC-Pad1)") (class "Default")
      (node (ref "J-IC") (pin "1") (pinfunction "1_1") (pintype "passive"))
      (node (ref "RR5") (pin "2") (pinfunction "2_2") (pintype "passive"))
    )
    (net (code "51") (name "Net-(J-IC-Pad2)") (class "Default")
      (node (ref "J-IC") (pin "2") (pinfunction "2_2") (pintype "passive"))
      (node (ref "RR7") (pin "2") (pinfunction "2_2") (pintype "passive"))
    )
    (net (code "52") (name "Net-(J-IN-Pad1)") (class "Default")
      (node (ref "J-IN") (pin "1") (pinfunction "1_1") (pintype "passive"))
      (node (ref "RR6") (pin "2") (pinfunction "2_2") (pintype "passive"))
    )
    (net (code "53") (name "Net-(J-IN-Pad2)") (class "Default")
      (node (ref "J-IN") (pin "2") (pinfunction "2_2") (pintype "passive"))
      (node (ref "RR8") (pin "2") (pinfunction "2_2") (pintype "passive"))
    )
    (net (code "54") (name "Net-(R2-Pad2)") (class "Default")
      (node (ref "R2") (pin "2") (pinfunction "2_2") (pintype "passive"))
      (node (ref "RC1") (pin "2") (pinfunction "2_2") (pintype "passive"))
      (node (ref "RR1") (pin "1") (pinfunction "1_1") (pintype "passive"))
    )
    (net (code "55") (name "Net-(R3-Pad1)") (class "Default")
      (node (ref "R3") (pin "1") (pinfunction "1_1") (pintype "passive"))
      (node (ref "RC2") (pin "2") (pinfunction "2_2") (pintype "passive"))
      (node (ref "RR2") (pin "1") (pinfunction "1_1") (pintype "passive"))
    )
    (net (code "56") (name "Net-(R10-Pad2)") (class "Default")
      (node (ref "R10") (pin "2") (pinfunction "2_2") (pintype "passive"))
      (node (ref "RC3") (pin "1") (pinfunction "1_1") (pintype "passive"))
      (node (ref "RR3") (pin "1") (pinfunction "1_1") (pintype "passive"))
    )
    (net (code "57") (name "Net-(R11-Pad1)") (class "Default")
      (node (ref "R11") (pin "1") (pinfunction "1_1") (pintype "passive"))
      (node (ref "RC4") (pin "1") (pinfunction "1_1") (pintype "passive"))
      (node (ref "RR4") (pin "1") (pinfunction "1_1") (pintype "passive"))
    )
    (net (code "58") (name "Net-(R14-Pad1)") (class "Default")
      (node (ref "R14") (pin "1") (pinfunction "1_1") (pintype "passive"))
      (node (ref "RC5") (pin "2") (pinfunction "2_2") (pintype "passive"))
      (node (ref "RR5") (pin "1") (pinfunction "1_1") (pintype "passive"))
    )
    (net (code "59") (name "Net-(R15-Pad1)") (class "Default")
      (node (ref "R15") (pin "1") (pinfunction "1_1") (pintype "passive"))
      (node (ref "RC6") (pin "2") (pinfunction "2_2") (pintype "passive"))
      (node (ref "RR6") (pin "1") (pinfunction "1_1") (pintype "passive"))
    )
    (net (code "60") (name "Net-(R18-Pad1)") (class "Default")
      (node (ref "R18") (pin "1") (pinfunction "1_1") (pintype "passive"))
      (node (ref "RC7") (pin "1") (pinfunction "1_1") (pintype "passive"))
      (node (ref "RR7") (pin "1") (pinfunction "1_1") (pintype "passive"))
    )
    (net (code "61") (name "Net-(R19-Pad1)") (class "Default")
      (node (ref "R19") (pin "1") (pinfunction "1_1") (pintype "passive"))
      (node (ref "RC8") (pin "1") (pinfunction "1_1") (pintype "passive"))
      (node (ref "RR8") (pin "1") (pinfunction "1_1") (pintype "passive"))
    )
    (net (code "62") (name "Net-(R22-Pad1)") (class "Default")
      (node (ref "R22") (pin "1") (pinfunction "1_1") (pintype "passive"))
      (node (ref "R29") (pin "1") (pinfunction "1_1") (pintype "passive"))
    )
    (net (code "63") (name "Net-(R24-Pad2)") (class "Default")
      (node (ref "R24") (pin "2") (pinfunction "2_2") (pintype "passive"))
      (node (ref "R25") (pin "2") (pinfunction "2_2") (pintype "passive"))
    )
    (net (code "64") (name "Net-(R25-Pad1)") (class "Default")
      (node (ref "R25") (pin "1") (pinfunction "1_1") (pintype "passive"))
      (node (ref "R26") (pin "1") (pinfunction "1_1") (pintype "passive"))
    )
    (net (code "65") (name "Net-(R26-Pad2)") (class "Default")
      (node (ref "R26") (pin "2") (pinfunction "2_2") (pintype "passive"))
      (node (ref "R27") (pin "2") (pinfunction "2_2") (pintype "passive"))
    )
    (net (code "66") (name "Net-(R27-Pad1)") (class "Default")
      (node (ref "R27") (pin "1") (pinfunction "1_1") (pintype "passive"))
      (node (ref "R28") (pin "1") (pinfunction "1_1") (pintype "passive"))
    )
    (net (code "67") (name "Net-(R28-Pad2)") (class "Default")
      (node (ref "R28") (pin "2") (pinfunction "2_2") (pintype "passive"))
      (node (ref "R29") (pin "2") (pinfunction "2_2") (pintype "passive"))
    )
    (net (code "68") (name "Net-(R33-Pad2)") (class "Default")
      (node (ref "R33") (pin "2") (pinfunction "2_2") (pintype "passive"))
      (node (ref "R39") (pin "2") (pinfunction "2_2") (pintype "passive"))
    )
    (net (code "69") (name "Net-(R34-Pad1)") (class "Default")
      (node (ref "R34") (pin "1") (pinfunction "1_1") (pintype "passive"))
      (node (ref "R35") (pin "1") (pinfunction "1_1") (pintype "passive"))
    )
    (net (code "70") (name "Net-(R35-Pad2)") (class "Default")
      (node (ref "R35") (pin "2") (pinfunction "2_2") (pintype "passive"))
      (node (ref "R36") (pin "2") (pinfunction "2_2") (pintype "passive"))
    )
    (net (code "71") (name "Net-(R36-Pad1)") (class "Default")
      (node (ref "R36") (pin "1") (pinfunction "1_1") (pintype "passive"))
      (node (ref "R37") (pin "1") (pinfunction "1_1") (pintype "passive"))
    )
    (net (code "72") (name "Net-(R37-Pad2)") (class "Default")
      (node (ref "R37") (pin "2") (pinfunction "2_2") (pintype "passive"))
      (node (ref "R38") (pin "2") (pinfunction "2_2") (pintype "passive"))
    )
    (net (code "73") (name "Net-(R38-Pad1)") (class "Default")
      (node (ref "R38") (pin "1") (pinfunction "1_1") (pintype "passive"))
      (node (ref "R39") (pin "1") (pinfunction "1_1") (pintype "passive"))
    )
    (net (code "74") (name "Net-(R42-Pad2)") (class "Default")
      (node (ref "R42") (pin "2") (pinfunction "2_2") (pintype "passive"))
      (node (ref "R48") (pin "2") (pinfunction "2_2") (pintype "passive"))
    )
    (net (code "75") (name "Net-(R43-Pad1)") (class "Default")
      (node (ref "R43") (pin "1") (pinfunction "1_1") (pintype "passive"))
      (node (ref "R44") (pin "1") (pinfunction "1_1") (pintype "passive"))
    )
    (net (code "76") (name "Net-(R44-Pad2)") (class "Default")
      (node (ref "R44") (pin "2") (pinfunction "2_2") (pintype "passive"))
      (node (ref "R45") (pin "2") (pinfunction "2_2") (pintype "passive"))
    )
    (net (code "77") (name "Net-(R45-Pad1)") (class "Default")
      (node (ref "R45") (pin "1") (pinfunction "1_1") (pintype "passive"))
      (node (ref "R46") (pin "1") (pinfunction "1_1") (pintype "passive"))
    )
    (net (code "78") (name "Net-(R46-Pad2)") (class "Default")
      (node (ref "R46") (pin "2") (pinfunction "2_2") (pintype "passive"))
      (node (ref "R47") (pin "2") (pinfunction "2_2") (pintype "passive"))
    )
    (net (code "79") (name "Net-(R47-Pad1)") (class "Default")
      (node (ref "R47") (pin "1") (pinfunction "1_1") (pintype "passive"))
      (node (ref "R48") (pin "1") (pinfunction "1_1") (pintype "passive"))
    )
    (net (code "80") (name "Net-(U1-+Vout)") (class "Default")
      (node (ref "C2") (pin "1") (pinfunction "1_1") (pintype "passive"))
      (node (ref "C5") (pin "2") (pintype "passive"))
      (node (ref "C6") (pin "2") (pintype "passive"))
      (node (ref "D1") (pin "A") (pintype "passive"))
      (node (ref "U1") (pin "2") (pinfunction "+Vout_2") (pintype "passive"))
    )
    (net (code "81") (name "Net-(U1-L)") (class "Default")
      (node (ref "C1") (pin "2") (pintype "passive"))
      (node (ref "JP1") (pin "2") (pinfunction "2_2") (pintype "passive"))
      (node (ref "RV1") (pin "2") (pinfunction "2_2") (pintype "passive"))
      (node (ref "U1") (pin "5") (pinfunction "L_5") (pintype "passive"))
    )
    (net (code "82") (name "Net-(U2-OUT)") (class "Default")
      (node (ref "3.3V") (pin "1") (pinfunction "1_1") (pintype "passive"))
      (node (ref "C4") (pin "1") (pintype "passive"))
      (node (ref "C8") (pin "2") (pintype "passive"))
      (node (ref "JP2") (pin "1") (pinfunction "1_1") (pintype "passive"))
      (node (ref "JP3") (pin "1") (pinfunction "1_1") (pintype "passive"))
      (node (ref "R1") (pin "2") (pinfunction "2_2") (pintype "passive"))
      (node (ref "U2") (pin "1") (pinfunction "OUT_1") (pintype "passive"))
    )
    (net (code "83") (name "Net-(U3-A)") (class "Default")
      (node (ref "JP4") (pin "2") (pinfunction "2_2") (pintype "passive"))
      (node (ref "U3") (pin "1") (pinfunction "A_1") (pintype "passive"))
    )
    (net (code "84") (name "Net-(U3-C)") (class "Default")
      (node (ref "J4") (pin "1") (pinfunction "1_1") (pintype "passive"))
      (node (ref "U3") (pin "4") (pinfunction "C_4") (pintype "passive"))
    )
    (net (code "85") (name "Net-(U3-E)") (class "Default")
      (node (ref "J4") (pin "2") (pinfunction "2_2") (pintype "passive"))
      (node (ref "U3") (pin "3") (pinfunction "E_3") (pintype "passive"))
    )
    (net (code "86") (name "Net-(U3-K)") (class "Default")
      (node (ref "R5") (pin "2") (pinfunction "2_2") (pintype "passive"))
      (node (ref "U3") (pin "2") (pinfunction "K_2") (pintype "passive"))
    )
    (net (code "87") (name "Net-(U4-A)") (class "Default")
      (node (ref "JP5") (pin "2") (pinfunction "2_2") (pintype "passive"))
      (node (ref "U4") (pin "1") (pinfunction "A_1") (pintype "passive"))
    )
    (net (code "88") (name "Net-(U4-C)") (class "Default")
      (node (ref "J4") (pin "3") (pinfunction "3_3") (pintype "passive"))
      (node (ref "U4") (pin "4") (pinfunction "C_4") (pintype "passive"))
    )
    (net (code "89") (name "Net-(U4-E)") (class "Default")
      (node (ref "J4") (pin "4") (pinfunction "4_4") (pintype "passive"))
      (node (ref "U4") (pin "3") (pinfunction "E_3") (pintype "passive"))
    )
    (net (code "90") (name "Net-(U4-K)") (class "Default")
      (node (ref "R16") (pin "2") (pinfunction "2_2") (pintype "passive"))
      (node (ref "U4") (pin "2") (pinfunction "K_2") (pintype "passive"))
    )
    (net (code "91") (name "Net-(U5-A)") (class "Default")
      (node (ref "JP6") (pin "2") (pinfunction "2_2") (pintype "passive"))
      (node (ref "U5") (pin "1") (pinfunction "A_1") (pintype "passive"))
    )
    (net (code "92") (name "Net-(U5-C)") (class "Default")
      (node (ref "J4") (pin "5") (pinfunction "5_5") (pintype "passive"))
      (node (ref "U5") (pin "4") (pinfunction "C_4") (pintype "passive"))
    )
    (net (code "93") (name "Net-(U5-E)") (class "Default")
      (node (ref "J4") (pin "6") (pinfunction "6_6") (pintype "passive"))
      (node (ref "U5") (pin "3") (pinfunction "E_3") (pintype "passive"))
    )
    (net (code "94") (name "Net-(U5-K)") (class "Default")
      (node (ref "R20") (pin "2") (pinfunction "2_2") (pintype "passive"))
      (node (ref "U5") (pin "2") (pinfunction "K_2") (pintype "passive"))
    )
    (net (code "95") (name "Net-(U6-A)") (class "Default")
      (node (ref "JP7") (pin "2") (pinfunction "2_2") (pintype "passive"))
      (node (ref "U6") (pin "1") (pinfunction "A_1") (pintype "passive"))
    )
    (net (code "96") (name "Net-(U6-C)") (class "Default")
      (node (ref "J4") (pin "7") (pinfunction "7_7") (pintype "passive"))
      (node (ref "U6") (pin "4") (pinfunction "C_4") (pintype "passive"))
    )
    (net (code "97") (name "Net-(U6-E)") (class "Default")
      (node (ref "J4") (pin "8") (pinfunction "8_8") (pintype "passive"))
      (node (ref "U6") (pin "3") (pinfunction "E_3") (pintype "passive"))
    )
    (net (code "98") (name "Net-(U6-K)") (class "Default")
      (node (ref "R23") (pin "2") (pinfunction "2_2") (pintype "passive"))
      (node (ref "U6") (pin "2") (pinfunction "K_2") (pintype "passive"))
    )
    (net (code "99") (name "Net-(U7-DVDD18)") (class "Default")
      (node (ref "C12") (pin "1") (pintype "passive"))
      (node (ref "C15") (pin "2") (pintype "passive"))
      (node (ref "U7") (pin "42") (pinfunction "VPP_42") (pintype "passive"))
      (node (ref "U7") (pin "43") (pinfunction "DVDD18_43") (pintype "passive"))
    )
    (net (code "100") (name "Net-(U7-OSCI)") (class "Default")
      (node (ref "U7") (pin "20") (pinfunction "OSCI_20") (pintype "passive"))
      (node (ref "X1") (pin "2") (pintype "passive"))
    )
    (net (code "101") (name "Net-(U7-OSCO)") (class "Default")
      (node (ref "U7") (pin "21") (pinfunction "OSCO_21") (pintype "passive"))
      (node (ref "X1") (pin "1") (pintype "passive"))
    )
    (net (code "102") (name "Net-(U7-Vref)") (class "Default")
      (node (ref "C22") (pin "2") (pintype "passive"))
      (node (ref "C23") (pin "2") (pintype "passive"))
      (node (ref "U7") (pin "11") (pinfunction "Vref_11") (pintype "passive"))
      (node (ref "VREF") (pin "1") (pinfunction "1_1") (pintype "passive"))
    )
    (net (code "103") (name "Net-(U7-~{RST})") (class "Default")
      (node (ref "C9") (pin "2") (pintype "passive"))
      (node (ref "JP8") (pin "1") (pinfunction "1_1") (pintype "passive"))
      (node (ref "R4") (pin "1") (pinfunction "1_1") (pintype "passive"))
      (node (ref "U7") (pin "41") (pinfunction "~{RST}_41") (pintype "passive"))
    )
    (net (code "104") (name "VCC") (class "Default")
      (node (ref "C3") (pin "1") (pintype "passive"))
      (node (ref "C7") (pin "2") (pintype "passive"))
      (node (ref "D1") (pin "K") (pintype "passive"))
      (node (ref "D2") (pin "K") (pintype "passive"))
      (node (ref "J3") (pin "1") (pinfunction "1_1") (pintype "passive"))
      (node (ref "U2") (pin "3") (pinfunction "IN_3") (pintype "passive"))
      (node (ref "VCC") (pin "1") (pinfunction "1_1") (pintype "passive"))
    )
    (net (code "105") (name "unconnected-(U1-NC-Pad1)") (class "Default")
      (node (ref "U1") (pin "1") (pinfunction "NC_1") (pintype "passive"))
    )
    (net (code "106") (name "unconnected-(U1-NC-Pad4)") (class "Default")
      (node (ref "U1") (pin "4") (pinfunction "NC_4") (pintype "passive"))
    )
    (net (code "107") (name "unconnected-(U1-NC-Pad7)") (class "Default")
      (node (ref "U1") (pin "7") (pinfunction "NC_7") (pintype "passive"))
    )
  )
)
